# gbikePCB.net
KiCad netlist of a schematic drawn in EAGLE
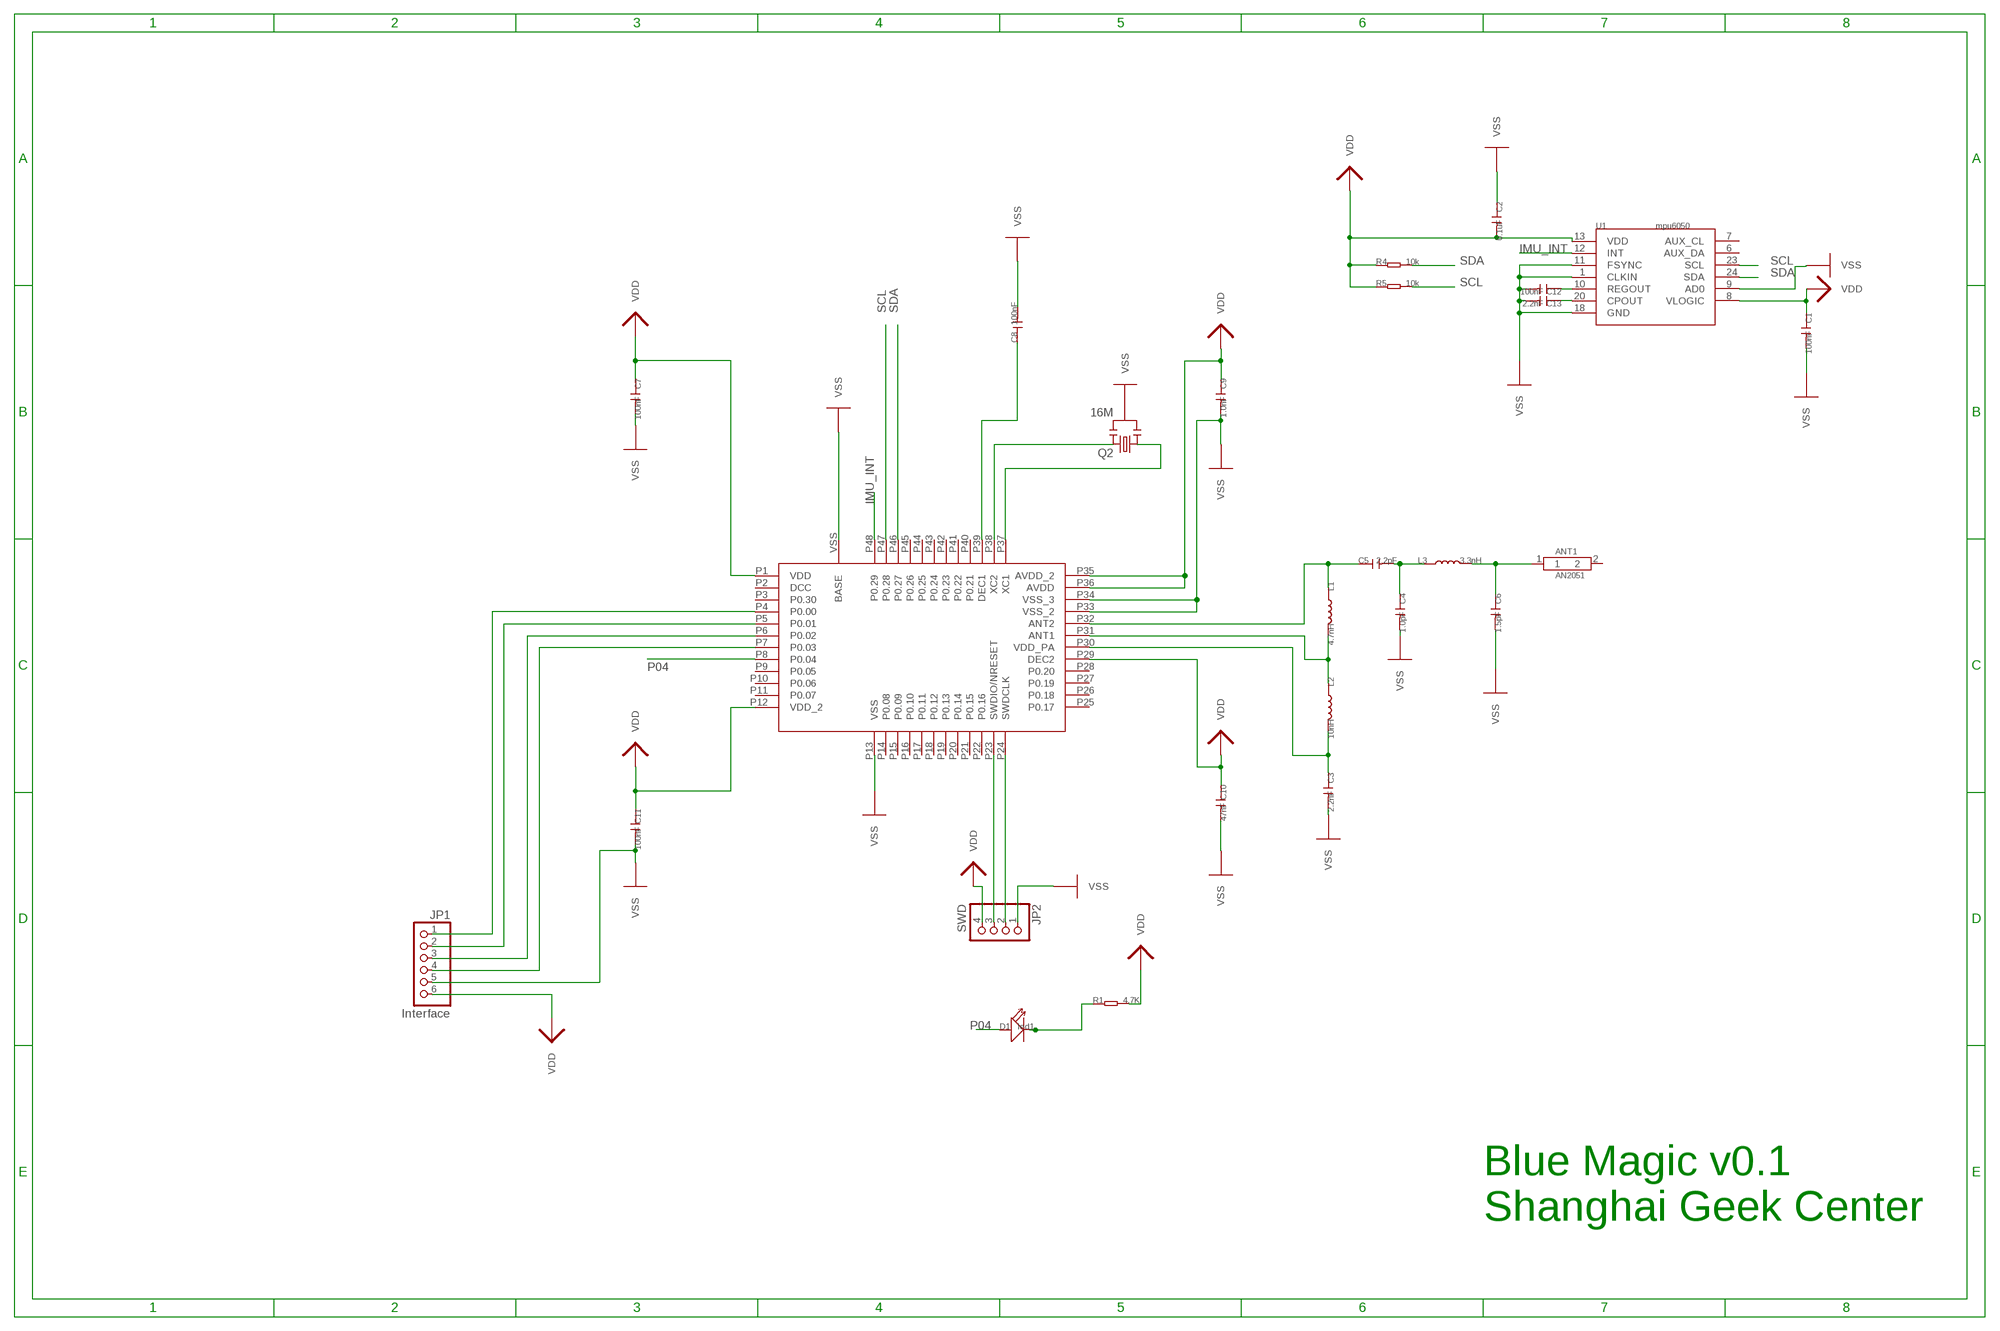
[diagram p0: schematic, sheet 1]

(export (version "E")
  (design (tool "Eeschema 10.0.6"))
  (components
    (comp (ref "ANT1")
      (value "AN2051")
      (footprint "eagle-import:CONNECTOR_2P-SMD-L5.05_W.02_H1.07MM")
      (libsource (lib "eagle-import") (part "CONNECTOR_ANTENNA-2.4GHZ-0.5DBIAN2051"))
    )
    (comp (ref "C1")
      (value "100nF")
      (footprint "eagle-import:DISCRETE_C0603")
      (libsource (lib "eagle-import") (part "DISCRETE_C-0603"))
    )
    (comp (ref "C2")
      (value "0.1uF")
      (footprint "eagle-import:DISCRETE_C0603")
      (libsource (lib "eagle-import") (part "DISCRETE_C-0603"))
    )
    (comp (ref "C3")
      (value "2.2nF")
      (footprint "eagle-import:DISCRETE_C0603")
      (libsource (lib "eagle-import") (part "DISCRETE_C-0603"))
    )
    (comp (ref "C4")
      (value "1.0pF")
      (footprint "eagle-import:DISCRETE_C0603")
      (libsource (lib "eagle-import") (part "DISCRETE_C-0603"))
    )
    (comp (ref "C5")
      (value "2.2pF")
      (footprint "eagle-import:DISCRETE_C0603")
      (libsource (lib "eagle-import") (part "DISCRETE_C-0603"))
    )
    (comp (ref "C6")
      (value "1.5pF")
      (footprint "eagle-import:DISCRETE_C0603")
      (libsource (lib "eagle-import") (part "DISCRETE_C-0603"))
    )
    (comp (ref "C7")
      (value "100nF")
      (footprint "eagle-import:DISCRETE_C0603")
      (libsource (lib "eagle-import") (part "DISCRETE_C-0603"))
    )
    (comp (ref "C8")
      (value "100nF")
      (footprint "eagle-import:DISCRETE_C0603")
      (libsource (lib "eagle-import") (part "DISCRETE_C-0603"))
    )
    (comp (ref "C9")
      (value "1.0nF")
      (footprint "eagle-import:DISCRETE_C0603")
      (libsource (lib "eagle-import") (part "DISCRETE_C-0603"))
    )
    (comp (ref "C10")
      (value "47nF")
      (footprint "eagle-import:DISCRETE_C0603")
      (libsource (lib "eagle-import") (part "DISCRETE_C-0603"))
    )
    (comp (ref "C11")
      (value "100nF")
      (footprint "eagle-import:DISCRETE_C0603")
      (libsource (lib "eagle-import") (part "DISCRETE_C-0603"))
    )
    (comp (ref "C12")
      (value "100nF")
      (footprint "eagle-import:DISCRETE_C0603")
      (libsource (lib "eagle-import") (part "DISCRETE_C-0603"))
    )
    (comp (ref "C13")
      (value "2.2nF")
      (footprint "eagle-import:DISCRETE_C0603")
      (libsource (lib "eagle-import") (part "DISCRETE_C-0603"))
    )
    (comp (ref "D1")
      (value "led1")
      (footprint "eagle-import:DISCRETE_LED-0603")
      (libsource (lib "eagle-import") (part "DISCRETE_LED0603"))
    )
    (comp (ref "JP1")
      (value "Interface")
      (footprint "eagle-import:1X06")
      (libsource (lib "eagle-import") (part "PINHD-1X6"))
    )
    (comp (ref "JP2")
      (value "SWD")
      (footprint "eagle-import:1X04")
      (libsource (lib "eagle-import") (part "PINHD-1X4"))
    )
    (comp (ref "L1")
      (value "4.7nH")
      (footprint "eagle-import:DISCRETE_L0603")
      (libsource (lib "eagle-import") (part "DISCRETE_L0603"))
    )
    (comp (ref "L2")
      (value "10nH")
      (footprint "eagle-import:DISCRETE_L0603")
      (libsource (lib "eagle-import") (part "DISCRETE_L0603"))
    )
    (comp (ref "L3")
      (value "3.3nH")
      (footprint "eagle-import:DISCRETE_L0603")
      (libsource (lib "eagle-import") (part "DISCRETE_L0603"))
    )
    (comp (ref "NRF51822")
      (value "nRF51822")
      (footprint "eagle-import:NRF51822_NRF51822_QFN48")
      (libsource (lib "eagle-import") (part "NRF51822_NRF51822_NRF51822"))
    )
    (comp (ref "Q2")
      (value "16M")
      (footprint "eagle-import:DIYDRONES3_RESONATOR-SMD")
      (libsource (lib "eagle-import") (part "DIYDRONES3_RESONATORSMD"))
    )
    (comp (ref "R1")
      (value "4.7K")
      (footprint "eagle-import:DISCRETE_R0603")
      (libsource (lib "eagle-import") (part "DISCRETE_R-0603"))
    )
    (comp (ref "R4")
      (value "10k")
      (footprint "eagle-import:DISCRETE_R0603")
      (libsource (lib "eagle-import") (part "DISCRETE_R-0603"))
    )
    (comp (ref "R5")
      (value "10k")
      (footprint "eagle-import:DISCRETE_R0603")
      (libsource (lib "eagle-import") (part "DISCRETE_R-0603"))
    )
    (comp (ref "U1")
      (value "mpu6050")
      (footprint "eagle-import:TINY_BLE_V1.0_TEMPLATE_QFN24")
      (libsource (lib "eagle-import") (part "TINY_BLE_V1.0_TEMPLATE_MPU-6050???¡¥"))
    )
  )
  (nets
    (net (code "1") (name "/IMU_INT") (class "Default")
      (node (ref "NRF51822") (pin "P48") (pinfunction "P0.29_P48") (pintype "bidirectional"))
      (node (ref "U1") (pin "12") (pinfunction "INT_12") (pintype "bidirectional"))
    )
    (net (code "2") (name "/P04") (class "Default")
      (node (ref "D1") (pin "+") (pinfunction "+_+") (pintype "passive"))
      (node (ref "NRF51822") (pin "P8") (pinfunction "P0.04_P8") (pintype "bidirectional"))
    )
    (net (code "3") (name "/SCL") (class "Default")
      (node (ref "NRF51822") (pin "P47") (pinfunction "P0.28_P47") (pintype "bidirectional"))
      (node (ref "R5") (pin "2") (pinfunction "2_2") (pintype "passive"))
      (node (ref "U1") (pin "23") (pinfunction "SCL_23") (pintype "bidirectional"))
    )
    (net (code "4") (name "/SDA") (class "Default")
      (node (ref "NRF51822") (pin "P46") (pinfunction "P0.27_P46") (pintype "bidirectional"))
      (node (ref "R4") (pin "2") (pinfunction "2_2") (pintype "passive"))
      (node (ref "U1") (pin "24") (pinfunction "SDA_24") (pintype "bidirectional"))
    )
    (net (code "5") (name "Net-(ANT1-Pad1)") (class "Default")
      (node (ref "ANT1") (pin "1") (pinfunction "1_1") (pintype "bidirectional"))
      (node (ref "C6") (pin "1") (pinfunction "1_1") (pintype "passive"))
      (node (ref "L3") (pin "2") (pinfunction "2_2") (pintype "passive"))
    )
    (net (code "6") (name "Net-(C4-Pad1)") (class "Default")
      (node (ref "C4") (pin "1") (pinfunction "1_1") (pintype "passive"))
      (node (ref "C5") (pin "2") (pinfunction "2_2") (pintype "passive"))
      (node (ref "L3") (pin "1") (pinfunction "1_1") (pintype "passive"))
    )
    (net (code "7") (name "Net-(D1-Pad-)") (class "Default")
      (node (ref "D1") (pin "-") (pinfunction "-_-") (pintype "passive"))
      (node (ref "R1") (pin "1") (pinfunction "1_1") (pintype "passive"))
    )
    (net (code "8") (name "Net-(NRF51822-ANT1)") (class "Default")
      (node (ref "L1") (pin "2") (pinfunction "2_2") (pintype "passive"))
      (node (ref "L2") (pin "1") (pinfunction "1_1") (pintype "passive"))
      (node (ref "NRF51822") (pin "P31") (pinfunction "ANT1_P31") (pintype "bidirectional"))
    )
    (net (code "9") (name "Net-(NRF51822-ANT2)") (class "Default")
      (node (ref "C5") (pin "1") (pinfunction "1_1") (pintype "passive"))
      (node (ref "L1") (pin "1") (pinfunction "1_1") (pintype "passive"))
      (node (ref "NRF51822") (pin "P32") (pinfunction "ANT2_P32") (pintype "bidirectional"))
    )
    (net (code "10") (name "Net-(NRF51822-DEC1)") (class "Default")
      (node (ref "C8") (pin "1") (pinfunction "1_1") (pintype "passive"))
      (node (ref "NRF51822") (pin "P39") (pinfunction "DEC1_P39") (pintype "bidirectional"))
    )
    (net (code "11") (name "Net-(NRF51822-P0.00)") (class "Default")
      (node (ref "JP1") (pin "1") (pinfunction "1_1") (pintype "passive"))
      (node (ref "NRF51822") (pin "P4") (pinfunction "P0.00_P4") (pintype "bidirectional"))
    )
    (net (code "12") (name "Net-(NRF51822-P0.01)") (class "Default")
      (node (ref "JP1") (pin "2") (pinfunction "2_2") (pintype "passive"))
      (node (ref "NRF51822") (pin "P5") (pinfunction "P0.01_P5") (pintype "bidirectional"))
    )
    (net (code "13") (name "Net-(NRF51822-P0.02)") (class "Default")
      (node (ref "JP1") (pin "3") (pinfunction "3_3") (pintype "passive"))
      (node (ref "NRF51822") (pin "P6") (pinfunction "P0.02_P6") (pintype "bidirectional"))
    )
    (net (code "14") (name "Net-(NRF51822-P0.03)") (class "Default")
      (node (ref "JP1") (pin "4") (pinfunction "4_4") (pintype "passive"))
      (node (ref "NRF51822") (pin "P7") (pinfunction "P0.03_P7") (pintype "bidirectional"))
    )
    (net (code "15") (name "Net-(NRF51822-SWDCLK)") (class "Default")
      (node (ref "JP2") (pin "2") (pinfunction "2_2") (pintype "passive"))
      (node (ref "NRF51822") (pin "P24") (pinfunction "SWDCLK_P24") (pintype "bidirectional"))
    )
    (net (code "16") (name "Net-(NRF51822-SWDIO{slash}NRESET)") (class "Default")
      (node (ref "JP2") (pin "3") (pinfunction "3_3") (pintype "passive"))
      (node (ref "NRF51822") (pin "P23") (pinfunction "SWDIO/NRESET_P23") (pintype "bidirectional"))
    )
    (net (code "17") (name "Net-(NRF51822-VDD_PA)") (class "Default")
      (node (ref "C3") (pin "1") (pinfunction "1_1") (pintype "passive"))
      (node (ref "L2") (pin "2") (pinfunction "2_2") (pintype "passive"))
      (node (ref "NRF51822") (pin "P30") (pinfunction "VDD_PA_P30") (pintype "bidirectional"))
    )
    (net (code "18") (name "Net-(NRF51822-XC1)") (class "Default")
      (node (ref "NRF51822") (pin "P37") (pinfunction "XC1_P37") (pintype "bidirectional"))
      (node (ref "Q2") (pin "1") (pinfunction "1_1") (pintype "passive"))
    )
    (net (code "19") (name "Net-(NRF51822-XC2)") (class "Default")
      (node (ref "NRF51822") (pin "P38") (pinfunction "XC2_P38") (pintype "bidirectional"))
      (node (ref "Q2") (pin "3") (pinfunction "3_3") (pintype "passive"))
    )
    (net (code "20") (name "Net-(U1-CPOUT)") (class "Default")
      (node (ref "C13") (pin "1") (pinfunction "1_1") (pintype "passive"))
      (node (ref "U1") (pin "20") (pinfunction "CPOUT_20") (pintype "bidirectional"))
    )
    (net (code "21") (name "Net-(U1-REGOUT)") (class "Default")
      (node (ref "C12") (pin "1") (pinfunction "1_1") (pintype "passive"))
      (node (ref "U1") (pin "10") (pinfunction "REGOUT_10") (pintype "bidirectional"))
    )
    (net (code "22") (name "VDD") (class "Default")
      (node (ref "C1") (pin "1") (pinfunction "1_1") (pintype "passive"))
      (node (ref "C10") (pin "1") (pinfunction "1_1") (pintype "passive"))
      (node (ref "C11") (pin "1") (pinfunction "1_1") (pintype "passive"))
      (node (ref "C2") (pin "2") (pinfunction "2_2") (pintype "passive"))
      (node (ref "C7") (pin "1") (pinfunction "1_1") (pintype "passive"))
      (node (ref "C9") (pin "1") (pinfunction "1_1") (pintype "passive"))
      (node (ref "JP1") (pin "6") (pinfunction "6_6") (pintype "passive"))
      (node (ref "JP2") (pin "4") (pinfunction "4_4") (pintype "passive"))
      (node (ref "NRF51822") (pin "P1") (pinfunction "VDD_P1") (pintype "bidirectional"))
      (node (ref "NRF51822") (pin "P12") (pinfunction "VDD_2_P12") (pintype "bidirectional"))
      (node (ref "NRF51822") (pin "P29") (pinfunction "DEC2_P29") (pintype "bidirectional"))
      (node (ref "NRF51822") (pin "P35") (pinfunction "AVDD_2_P35") (pintype "bidirectional"))
      (node (ref "NRF51822") (pin "P36") (pinfunction "AVDD_P36") (pintype "bidirectional"))
      (node (ref "R1") (pin "2") (pinfunction "2_2") (pintype "passive"))
      (node (ref "R4") (pin "1") (pinfunction "1_1") (pintype "passive"))
      (node (ref "R5") (pin "1") (pinfunction "1_1") (pintype "passive"))
      (node (ref "U1") (pin "13") (pinfunction "VDD_13") (pintype "bidirectional"))
      (node (ref "U1") (pin "8") (pinfunction "VLOGIC_8") (pintype "bidirectional"))
    )
    (net (code "23") (name "VSS") (class "Default")
      (node (ref "C1") (pin "2") (pinfunction "2_2") (pintype "passive"))
      (node (ref "C10") (pin "2") (pinfunction "2_2") (pintype "passive"))
      (node (ref "C11") (pin "2") (pinfunction "2_2") (pintype "passive"))
      (node (ref "C12") (pin "2") (pinfunction "2_2") (pintype "passive"))
      (node (ref "C13") (pin "2") (pinfunction "2_2") (pintype "passive"))
      (node (ref "C2") (pin "1") (pinfunction "1_1") (pintype "passive"))
      (node (ref "C3") (pin "2") (pinfunction "2_2") (pintype "passive"))
      (node (ref "C4") (pin "2") (pinfunction "2_2") (pintype "passive"))
      (node (ref "C6") (pin "2") (pinfunction "2_2") (pintype "passive"))
      (node (ref "C7") (pin "2") (pinfunction "2_2") (pintype "passive"))
      (node (ref "C8") (pin "2") (pinfunction "2_2") (pintype "passive"))
      (node (ref "C9") (pin "2") (pinfunction "2_2") (pintype "passive"))
      (node (ref "JP1") (pin "5") (pinfunction "5_5") (pintype "passive"))
      (node (ref "JP2") (pin "1") (pinfunction "1_1") (pintype "passive"))
      (node (ref "NRF51822") (pin "P13") (pinfunction "VSS_P13") (pintype "bidirectional"))
      (node (ref "NRF51822") (pin "P33") (pinfunction "VSS_2_P33") (pintype "bidirectional"))
      (node (ref "NRF51822") (pin "P34") (pinfunction "VSS_3_P34") (pintype "bidirectional"))
      (node (ref "NRF51822") (pin "VSS") (pinfunction "BASE_VSS") (pintype "bidirectional"))
      (node (ref "Q2") (pin "2") (pinfunction "2_2") (pintype "passive"))
      (node (ref "U1") (pin "1") (pinfunction "CLKIN_1") (pintype "bidirectional"))
      (node (ref "U1") (pin "11") (pinfunction "FSYNC_11") (pintype "bidirectional"))
      (node (ref "U1") (pin "18") (pinfunction "GND_18") (pintype "bidirectional"))
      (node (ref "U1") (pin "9") (pinfunction "AD0_9") (pintype "bidirectional"))
    )
    (net (code "24") (name "unconnected-(ANT1-Pad2)") (class "Default")
      (node (ref "ANT1") (pin "2") (pinfunction "2_2") (pintype "bidirectional"))
    )
    (net (code "25") (name "unconnected-(NRF51822-DCC-PadP2)") (class "Default")
      (node (ref "NRF51822") (pin "P2") (pinfunction "DCC_P2") (pintype "bidirectional"))
    )
    (net (code "26") (name "unconnected-(NRF51822-P0.05-PadP9)") (class "Default")
      (node (ref "NRF51822") (pin "P9") (pinfunction "P0.05_P9") (pintype "bidirectional"))
    )
    (net (code "27") (name "unconnected-(NRF51822-P0.06-PadP10)") (class "Default")
      (node (ref "NRF51822") (pin "P10") (pinfunction "P0.06_P10") (pintype "bidirectional"))
    )
    (net (code "28") (name "unconnected-(NRF51822-P0.07-PadP11)") (class "Default")
      (node (ref "NRF51822") (pin "P11") (pinfunction "P0.07_P11") (pintype "bidirectional"))
    )
    (net (code "29") (name "unconnected-(NRF51822-P0.08-PadP14)") (class "Default")
      (node (ref "NRF51822") (pin "P14") (pinfunction "P0.08_P14") (pintype "bidirectional"))
    )
    (net (code "30") (name "unconnected-(NRF51822-P0.09-PadP15)") (class "Default")
      (node (ref "NRF51822") (pin "P15") (pinfunction "P0.09_P15") (pintype "bidirectional"))
    )
    (net (code "31") (name "unconnected-(NRF51822-P0.10-PadP16)") (class "Default")
      (node (ref "NRF51822") (pin "P16") (pinfunction "P0.10_P16") (pintype "bidirectional"))
    )
    (net (code "32") (name "unconnected-(NRF51822-P0.11-PadP17)") (class "Default")
      (node (ref "NRF51822") (pin "P17") (pinfunction "P0.11_P17") (pintype "bidirectional"))
    )
    (net (code "33") (name "unconnected-(NRF51822-P0.12-PadP18)") (class "Default")
      (node (ref "NRF51822") (pin "P18") (pinfunction "P0.12_P18") (pintype "bidirectional"))
    )
    (net (code "34") (name "unconnected-(NRF51822-P0.13-PadP19)") (class "Default")
      (node (ref "NRF51822") (pin "P19") (pinfunction "P0.13_P19") (pintype "bidirectional"))
    )
    (net (code "35") (name "unconnected-(NRF51822-P0.14-PadP20)") (class "Default")
      (node (ref "NRF51822") (pin "P20") (pinfunction "P0.14_P20") (pintype "bidirectional"))
    )
    (net (code "36") (name "unconnected-(NRF51822-P0.15-PadP21)") (class "Default")
      (node (ref "NRF51822") (pin "P21") (pinfunction "P0.15_P21") (pintype "bidirectional"))
    )
    (net (code "37") (name "unconnected-(NRF51822-P0.16-PadP22)") (class "Default")
      (node (ref "NRF51822") (pin "P22") (pinfunction "P0.16_P22") (pintype "bidirectional"))
    )
    (net (code "38") (name "unconnected-(NRF51822-P0.17-PadP25)") (class "Default")
      (node (ref "NRF51822") (pin "P25") (pinfunction "P0.17_P25") (pintype "bidirectional"))
    )
    (net (code "39") (name "unconnected-(NRF51822-P0.18-PadP26)") (class "Default")
      (node (ref "NRF51822") (pin "P26") (pinfunction "P0.18_P26") (pintype "bidirectional"))
    )
    (net (code "40") (name "unconnected-(NRF51822-P0.19-PadP27)") (class "Default")
      (node (ref "NRF51822") (pin "P27") (pinfunction "P0.19_P27") (pintype "bidirectional"))
    )
    (net (code "41") (name "unconnected-(NRF51822-P0.20-PadP28)") (class "Default")
      (node (ref "NRF51822") (pin "P28") (pinfunction "P0.20_P28") (pintype "bidirectional"))
    )
    (net (code "42") (name "unconnected-(NRF51822-P0.21-PadP40)") (class "Default")
      (node (ref "NRF51822") (pin "P40") (pinfunction "P0.21_P40") (pintype "bidirectional"))
    )
    (net (code "43") (name "unconnected-(NRF51822-P0.22-PadP41)") (class "Default")
      (node (ref "NRF51822") (pin "P41") (pinfunction "P0.22_P41") (pintype "bidirectional"))
    )
    (net (code "44") (name "unconnected-(NRF51822-P0.23-PadP42)") (class "Default")
      (node (ref "NRF51822") (pin "P42") (pinfunction "P0.23_P42") (pintype "bidirectional"))
    )
    (net (code "45") (name "unconnected-(NRF51822-P0.24-PadP43)") (class "Default")
      (node (ref "NRF51822") (pin "P43") (pinfunction "P0.24_P43") (pintype "bidirectional"))
    )
    (net (code "46") (name "unconnected-(NRF51822-P0.25-PadP44)") (class "Default")
      (node (ref "NRF51822") (pin "P44") (pinfunction "P0.25_P44") (pintype "bidirectional"))
    )
    (net (code "47") (name "unconnected-(NRF51822-P0.26-PadP45)") (class "Default")
      (node (ref "NRF51822") (pin "P45") (pinfunction "P0.26_P45") (pintype "bidirectional"))
    )
    (net (code "48") (name "unconnected-(NRF51822-P0.30-PadP3)") (class "Default")
      (node (ref "NRF51822") (pin "P3") (pinfunction "P0.30_P3") (pintype "bidirectional"))
    )
    (net (code "49") (name "unconnected-(U1-AUX_CL-Pad7)") (class "Default")
      (node (ref "U1") (pin "7") (pinfunction "AUX_CL_7") (pintype "bidirectional"))
    )
    (net (code "50") (name "unconnected-(U1-AUX_DA-Pad6)") (class "Default")
      (node (ref "U1") (pin "6") (pinfunction "AUX_DA_6") (pintype "bidirectional"))
    )
  )
)
